# Pacman2.net
KiCad netlist of a schematic drawn in EAGLE
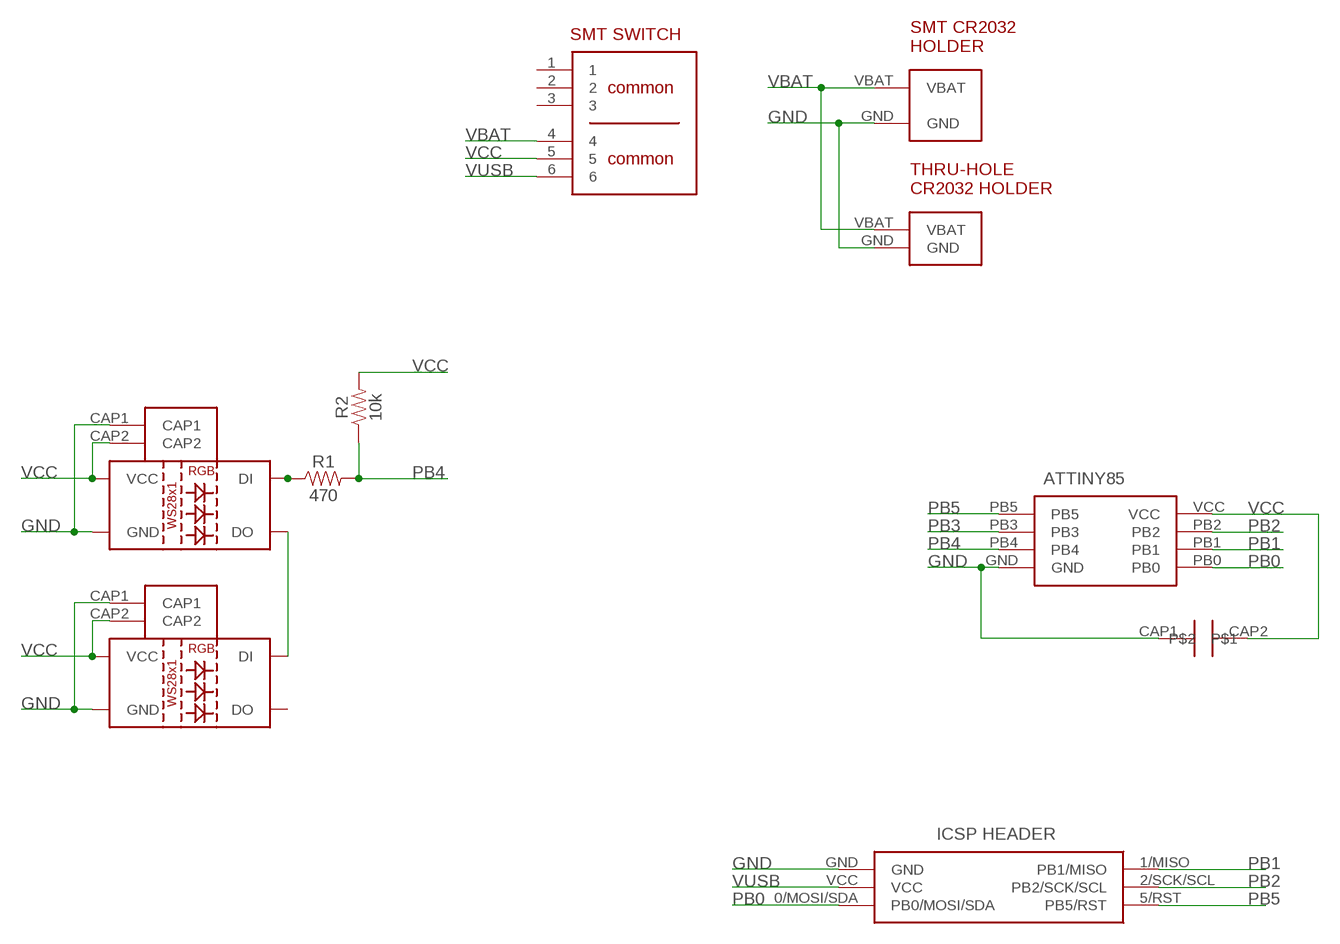
[diagram p0: schematic, sheet 1]

(export (version "E")
  (design (tool "Eeschema 10.0.6"))
  (components
    (comp (ref "D1")
      (value "WS2812B")
      (footprint "eagle-import:WS2812B")
      (libsource (lib "eagle-import") (part "WS2812B"))
    )
    (comp (ref "D2")
      (value "WS2812B")
      (footprint "eagle-import:WS2812B")
      (libsource (lib "eagle-import") (part "WS2812B"))
    )
    (comp (ref "DECOUPLER")
      (value ".1uf")
      (footprint "eagle-import:0603-CAP")
      (libsource (lib "eagle-import") (part "0603-CAP"))
    )
    (comp (ref "IC1")
      (value "ATTINY85-20SU")
      (footprint "eagle-import:SOT127P798X216-8N")
      (fields (field (name "RS_PART_NUMBER") "1331674"))
      (libsource (lib "eagle-import") (part "ATTINY85-20SU"))
    )
    (comp (ref "J2")
      (value "ICSP-LO-SILK")
      (footprint "eagle-import:ICSP-LO-SILK")
      (libsource (lib "eagle-import") (part "ICSP-LO-SILK"))
    )
    (comp (ref "R1")
      (value "470")
      (footprint "eagle-import:0603")
      (libsource (lib "eagle-import") (part "470OHM-0603-1/10W-1%"))
    )
    (comp (ref "R2")
      (value "10k")
      (footprint "eagle-import:0603")
      (libsource (lib "eagle-import") (part "10KOHM-0603-1/10W-1%"))
    )
    (comp (ref "U$2")
      (value "SMT-BATTERY-HOLDER")
      (footprint "eagle-import:SMT-CR-HOLDER")
      (libsource (lib "eagle-import") (part "SMT-BATTERY-HOLDER"))
    )
    (comp (ref "U$3")
      (value "THRU-CR-HOLDER")
      (footprint "eagle-import:THRU-CR-HOLDER")
      (libsource (lib "eagle-import") (part "THRU-CR-HOLDER"))
    )
    (comp (ref "U$145")
      (value "SMT-SWITCH")
      (footprint "eagle-import:SMT-SWITCH")
      (libsource (lib "eagle-import") (part "SMT-SWITCH"))
    )
  )
  (nets
    (net (code "1") (name "/GND") (class "Default")
      (node (ref "D1") (pin "CAP1") (pinfunction "CAP1_CAP1") (pintype "bidirectional"))
      (node (ref "D1") (pin "GND") (pinfunction "GND_GND") (pintype "bidirectional"))
      (node (ref "D2") (pin "CAP1") (pinfunction "CAP1_CAP1") (pintype "bidirectional"))
      (node (ref "D2") (pin "GND") (pinfunction "GND_GND") (pintype "bidirectional"))
      (node (ref "DECOUPLER") (pin "CAP1") (pinfunction "P$1_CAP1") (pintype "bidirectional"))
      (node (ref "IC1") (pin "GND") (pinfunction "GND_GND") (pintype "bidirectional"))
      (node (ref "J2") (pin "GND") (pinfunction "GND_GND") (pintype "bidirectional"))
      (node (ref "U$2") (pin "GND") (pinfunction "GND_GND") (pintype "bidirectional"))
      (node (ref "U$3") (pin "GND") (pinfunction "GND_GND") (pintype "bidirectional"))
    )
    (net (code "2") (name "/PB0") (class "Default")
      (node (ref "IC1") (pin "PB0") (pinfunction "PB0_PB0") (pintype "bidirectional"))
      (node (ref "J2") (pin "0/MOSI/SDA") (pinfunction "PB0/MOSI/SDA_0/MOSI/SDA") (pintype "bidirectional"))
    )
    (net (code "3") (name "/PB1") (class "Default")
      (node (ref "IC1") (pin "PB1") (pinfunction "PB1_PB1") (pintype "bidirectional"))
      (node (ref "J2") (pin "1/MISO") (pinfunction "PB1/MISO_1/MISO") (pintype "bidirectional"))
    )
    (net (code "4") (name "/PB2") (class "Default")
      (node (ref "IC1") (pin "PB2") (pinfunction "PB2_PB2") (pintype "bidirectional"))
      (node (ref "J2") (pin "2/SCK/SCL") (pinfunction "PB2/SCK/SCL_2/SCK/SCL") (pintype "bidirectional"))
    )
    (net (code "5") (name "/PB3") (class "Default")
      (node (ref "IC1") (pin "PB3") (pinfunction "PB3_PB3") (pintype "bidirectional"))
    )
    (net (code "6") (name "/PB4") (class "Default")
      (node (ref "IC1") (pin "PB4") (pinfunction "PB4_PB4") (pintype "bidirectional"))
      (node (ref "R1") (pin "2") (pinfunction "2_2") (pintype "passive"))
      (node (ref "R2") (pin "1") (pinfunction "1_1") (pintype "passive"))
    )
    (net (code "7") (name "/PB5") (class "Default")
      (node (ref "IC1") (pin "PB5") (pinfunction "PB5_PB5") (pintype "bidirectional"))
      (node (ref "J2") (pin "5/RST") (pinfunction "PB5/RST_5/RST") (pintype "bidirectional"))
    )
    (net (code "8") (name "/VBAT") (class "Default")
      (node (ref "U$145") (pin "4") (pinfunction "4_4") (pintype "bidirectional"))
      (node (ref "U$2") (pin "VBAT") (pinfunction "VBAT_VBAT") (pintype "bidirectional"))
      (node (ref "U$3") (pin "VBAT") (pinfunction "VBAT_VBAT") (pintype "bidirectional"))
    )
    (net (code "9") (name "/VCC") (class "Default")
      (node (ref "D1") (pin "CAP2") (pinfunction "CAP2_CAP2") (pintype "bidirectional"))
      (node (ref "D1") (pin "VCC") (pinfunction "VCC_VCC") (pintype "bidirectional"))
      (node (ref "D2") (pin "CAP2") (pinfunction "CAP2_CAP2") (pintype "bidirectional"))
      (node (ref "D2") (pin "VCC") (pinfunction "VCC_VCC") (pintype "bidirectional"))
      (node (ref "DECOUPLER") (pin "CAP2") (pinfunction "P$2_CAP2") (pintype "bidirectional"))
      (node (ref "IC1") (pin "VCC") (pinfunction "VCC_VCC") (pintype "bidirectional"))
      (node (ref "R2") (pin "2") (pinfunction "2_2") (pintype "passive"))
      (node (ref "U$145") (pin "5") (pinfunction "5_5") (pintype "bidirectional"))
    )
    (net (code "10") (name "/VUSB") (class "Default")
      (node (ref "J2") (pin "VCC") (pinfunction "VCC_VCC") (pintype "bidirectional"))
      (node (ref "U$145") (pin "6") (pinfunction "6_6") (pintype "bidirectional"))
    )
    (net (code "11") (name "Net-(D1-PadDI)") (class "Default")
      (node (ref "D1") (pin "DI") (pinfunction "DI_DI") (pintype "bidirectional"))
      (node (ref "R1") (pin "1") (pinfunction "1_1") (pintype "passive"))
    )
    (net (code "12") (name "Net-(D1-PadDO)") (class "Default")
      (node (ref "D1") (pin "DO") (pinfunction "DO_DO") (pintype "bidirectional"))
      (node (ref "D2") (pin "DI") (pinfunction "DI_DI") (pintype "bidirectional"))
    )
    (net (code "13") (name "unconnected-(D2-PadDO)") (class "Default")
      (node (ref "D2") (pin "DO") (pinfunction "DO_DO") (pintype "bidirectional"))
    )
    (net (code "14") (name "unconnected-(U$145-Pad1)") (class "Default")
      (node (ref "U$145") (pin "1") (pinfunction "1_1") (pintype "bidirectional"))
    )
    (net (code "15") (name "unconnected-(U$145-Pad2)") (class "Default")
      (node (ref "U$145") (pin "2") (pinfunction "2_2") (pintype "bidirectional"))
    )
    (net (code "16") (name "unconnected-(U$145-Pad3)") (class "Default")
      (node (ref "U$145") (pin "3") (pinfunction "3_3") (pintype "bidirectional"))
    )
  )
)
